# mahirAMPLIFER.net
KiCad netlist of a schematic drawn in Altium Designer
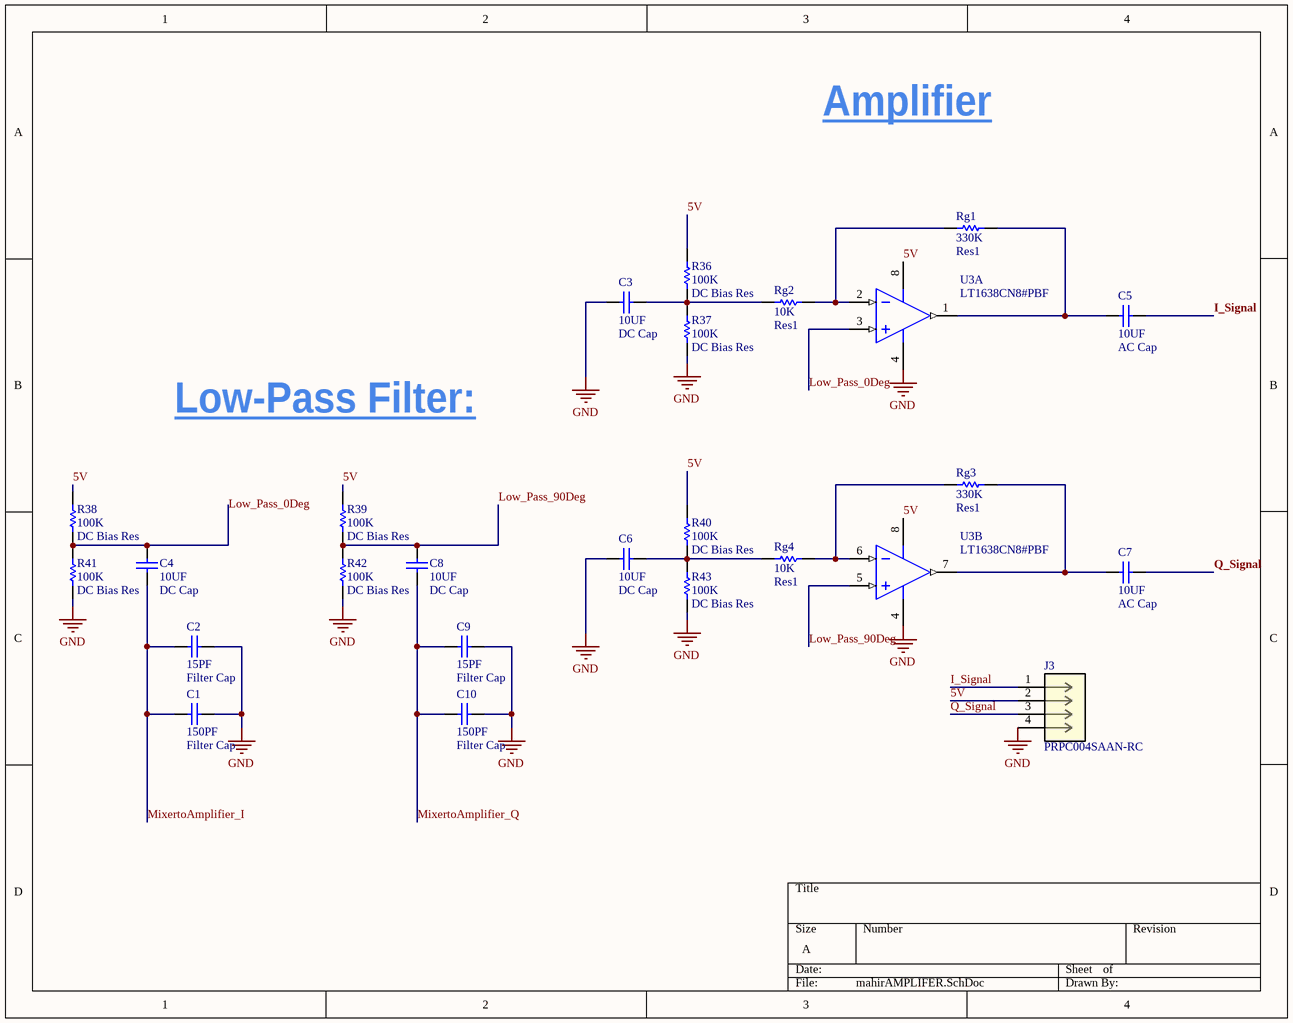
[diagram p0: mahirAMPLIFER.SchDoc]

(export (version "E")
  (design (tool "Eeschema 10.0.6"))
  (components
    (comp (ref "C1")
      (value "Filter Cap")
      (footprint "RADIAL-0.1")
      (description "Capacitor")
      (fields
        (field (name "ALTIUM_VALUE") "150PF")
        (field (name "MANUFACTURER PART NUMBER") "K151J15C0GF53L2")
        (field (name "PUBLISHER") "Altium Limited")
      )
      (libsource (lib "ECE295-Capacitors-TH") (part "CAP CER 150PF 50V C0G/NP0 RADIAL"))
    )
    (comp (ref "C2")
      (value "Filter Cap")
      (footprint "RADIAL-0.1")
      (description "Capacitor")
      (fields
        (field (name "ALTIUM_VALUE") "15PF")
        (field (name "MANUFACTURER PART NUMBER") "K150J15C0GF5TL2")
        (field (name "PUBLISHER") "Altium Limited")
      )
      (libsource (lib "ECE295-Capacitors-TH") (part "CAP CER 15PF 50V C0G/NP0 RADIAL"))
    )
    (comp (ref "C3")
      (value "DC Cap")
      (footprint "RADIAL-0.1")
      (description "Capacitor")
      (fields
        (field (name "ALTIUM_VALUE") "10UF")
        (field (name "MANUFACTURER PART NUMBER") "ESK106M063AC3FA")
        (field (name "PUBLISHER") "Altium Limited")
      )
      (libsource (lib "ECE295-Capacitors-TH") (part "CAP ALUM 10UF 20% 63V RADIAL"))
    )
    (comp (ref "C4")
      (value "DC Cap")
      (footprint "RADIAL-0.1")
      (description "Capacitor")
      (fields
        (field (name "ALTIUM_VALUE") "10UF")
        (field (name "MANUFACTURER PART NUMBER") "ESK106M063AC3FA")
        (field (name "PUBLISHER") "Altium Limited")
      )
      (libsource (lib "ECE295-Capacitors-TH") (part "CAP ALUM 10UF 20% 63V RADIAL"))
    )
    (comp (ref "C5")
      (value "AC Cap")
      (footprint "RADIAL-0.1")
      (description "Capacitor")
      (fields
        (field (name "ALTIUM_VALUE") "10UF")
        (field (name "MANUFACTURER PART NUMBER") "ESK106M063AC3FA")
        (field (name "PUBLISHER") "Altium Limited")
      )
      (libsource (lib "ECE295-Capacitors-TH") (part "CAP ALUM 10UF 20% 63V RADIAL"))
    )
    (comp (ref "C6")
      (value "DC Cap")
      (footprint "RADIAL-0.1")
      (description "Capacitor")
      (fields
        (field (name "ALTIUM_VALUE") "10UF")
        (field (name "MANUFACTURER PART NUMBER") "ESK106M063AC3FA")
        (field (name "PUBLISHER") "Altium Limited")
      )
      (libsource (lib "ECE295-Capacitors-TH") (part "CAP ALUM 10UF 20% 63V RADIAL"))
    )
    (comp (ref "C7")
      (value "AC Cap")
      (footprint "RADIAL-0.1")
      (description "Capacitor")
      (fields
        (field (name "ALTIUM_VALUE") "10UF")
        (field (name "MANUFACTURER PART NUMBER") "ESK106M063AC3FA")
        (field (name "PUBLISHER") "Altium Limited")
      )
      (libsource (lib "ECE295-Capacitors-TH") (part "CAP ALUM 10UF 20% 63V RADIAL"))
    )
    (comp (ref "C8")
      (value "DC Cap")
      (footprint "RADIAL-0.1")
      (description "Capacitor")
      (fields
        (field (name "ALTIUM_VALUE") "10UF")
        (field (name "MANUFACTURER PART NUMBER") "ESK106M063AC3FA")
        (field (name "PUBLISHER") "Altium Limited")
      )
      (libsource (lib "ECE295-Capacitors-TH") (part "CAP ALUM 10UF 20% 63V RADIAL"))
    )
    (comp (ref "C9")
      (value "Filter Cap")
      (footprint "RADIAL-0.1")
      (description "Capacitor")
      (fields
        (field (name "ALTIUM_VALUE") "15PF")
        (field (name "MANUFACTURER PART NUMBER") "K150J15C0GF5TL2")
        (field (name "PUBLISHER") "Altium Limited")
      )
      (libsource (lib "ECE295-Capacitors-TH") (part "CAP CER 15PF 50V C0G/NP0 RADIAL"))
    )
    (comp (ref "C10")
      (value "Filter Cap")
      (footprint "RADIAL-0.1")
      (description "Capacitor")
      (fields
        (field (name "ALTIUM_VALUE") "150PF")
        (field (name "MANUFACTURER PART NUMBER") "K151J15C0GF53L2")
        (field (name "PUBLISHER") "Altium Limited")
      )
      (libsource (lib "ECE295-Capacitors-TH") (part "CAP CER 150PF 50V C0G/NP0 RADIAL"))
    )
    (comp (ref "J3")
      (value "PRPC004SAAN-RC")
      (footprint "CONN4_PRPC004_SUL")
      (description "No Description Available")
      (libsource (lib "PRPC004SAAN-RC") (part "PRPC004SAAN-RC"))
    )
    (comp (ref "R36")
      (value "DC Bias Res")
      (footprint "AXIAL-0.1-RES")
      (description "Resistor")
      (fields
        (field (name "ALTIUM_VALUE") "100K")
        (field (name "MANUFACTURER PART NUMBER") "CFR-25JB-52-100K")
        (field (name "TOLERANCE") "0.05")
        (field (name "PUBLISHER") "Altium Limited")
      )
      (libsource (lib "ECE295-Resistors-TH") (part "RES 100K OHM 5% 1/4W AXIAL"))
    )
    (comp (ref "R37")
      (value "DC Bias Res")
      (footprint "AXIAL-0.1-RES")
      (description "Resistor")
      (fields
        (field (name "ALTIUM_VALUE") "100K")
        (field (name "MANUFACTURER PART NUMBER") "CFR-25JB-52-100K")
        (field (name "TOLERANCE") "0.05")
        (field (name "PUBLISHER") "Altium Limited")
      )
      (libsource (lib "ECE295-Resistors-TH") (part "RES 100K OHM 5% 1/4W AXIAL"))
    )
    (comp (ref "R38")
      (value "DC Bias Res")
      (footprint "AXIAL-0.1-RES")
      (description "Resistor")
      (fields
        (field (name "ALTIUM_VALUE") "100K")
        (field (name "MANUFACTURER PART NUMBER") "CFR-25JB-52-100K")
        (field (name "TOLERANCE") "0.05")
        (field (name "PUBLISHER") "Altium Limited")
      )
      (libsource (lib "ECE295-Resistors-TH") (part "RES 100K OHM 5% 1/4W AXIAL"))
    )
    (comp (ref "R39")
      (value "DC Bias Res")
      (footprint "AXIAL-0.1-RES")
      (description "Resistor")
      (fields
        (field (name "ALTIUM_VALUE") "100K")
        (field (name "MANUFACTURER PART NUMBER") "CFR-25JB-52-100K")
        (field (name "TOLERANCE") "0.05")
        (field (name "PUBLISHER") "Altium Limited")
      )
      (libsource (lib "ECE295-Resistors-TH") (part "RES 100K OHM 5% 1/4W AXIAL"))
    )
    (comp (ref "R40")
      (value "DC Bias Res")
      (footprint "AXIAL-0.1-RES")
      (description "Resistor")
      (fields
        (field (name "ALTIUM_VALUE") "100K")
        (field (name "MANUFACTURER PART NUMBER") "CFR-25JB-52-100K")
        (field (name "TOLERANCE") "0.05")
        (field (name "PUBLISHER") "Altium Limited")
      )
      (libsource (lib "ECE295-Resistors-TH") (part "RES 100K OHM 5% 1/4W AXIAL"))
    )
    (comp (ref "R41")
      (value "DC Bias Res")
      (footprint "AXIAL-0.1-RES")
      (description "Resistor")
      (fields
        (field (name "ALTIUM_VALUE") "100K")
        (field (name "MANUFACTURER PART NUMBER") "CFR-25JB-52-100K")
        (field (name "TOLERANCE") "0.05")
        (field (name "PUBLISHER") "Altium Limited")
      )
      (libsource (lib "ECE295-Resistors-TH") (part "RES 100K OHM 5% 1/4W AXIAL"))
    )
    (comp (ref "R42")
      (value "DC Bias Res")
      (footprint "AXIAL-0.1-RES")
      (description "Resistor")
      (fields
        (field (name "ALTIUM_VALUE") "100K")
        (field (name "MANUFACTURER PART NUMBER") "CFR-25JB-52-100K")
        (field (name "TOLERANCE") "0.05")
        (field (name "PUBLISHER") "Altium Limited")
      )
      (libsource (lib "ECE295-Resistors-TH") (part "RES 100K OHM 5% 1/4W AXIAL"))
    )
    (comp (ref "R43")
      (value "DC Bias Res")
      (footprint "AXIAL-0.1-RES")
      (description "Resistor")
      (fields
        (field (name "ALTIUM_VALUE") "100K")
        (field (name "MANUFACTURER PART NUMBER") "CFR-25JB-52-100K")
        (field (name "TOLERANCE") "0.05")
        (field (name "PUBLISHER") "Altium Limited")
      )
      (libsource (lib "ECE295-Resistors-TH") (part "RES 100K OHM 5% 1/4W AXIAL"))
    )
    (comp (ref "Rg1")
      (value "Res1")
      (footprint "AXIAL-0.1-RES")
      (description "Resistor")
      (fields
        (field (name "ALTIUM_VALUE") "330K")
        (field (name "MANUFACTURER PART NUMBER") "CFR-25JB-52-330K")
        (field (name "TOLERANCE") "0.05")
        (field (name "PUBLISHER") "Altium Limited")
      )
      (libsource (lib "ECE295-Resistors-TH") (part "RES 330K OHM 5% 1/4W AXIAL"))
    )
    (comp (ref "Rg2")
      (value "Res1")
      (footprint "AXIAL-0.1-RES")
      (description "Resistor")
      (fields
        (field (name "ALTIUM_VALUE") "10K")
        (field (name "MANUFACTURER PART NUMBER") "CFR-25JB-52-10K")
        (field (name "TOLERANCE") "0.05")
        (field (name "PUBLISHER") "Altium Limited")
      )
      (libsource (lib "ECE295-Resistors-TH") (part "RES 10K OHM 5% 1/4W AXIAL"))
    )
    (comp (ref "Rg3")
      (value "Res1")
      (footprint "AXIAL-0.1-RES")
      (description "Resistor")
      (fields
        (field (name "ALTIUM_VALUE") "330K")
        (field (name "MANUFACTURER PART NUMBER") "CFR-25JB-52-330K")
        (field (name "TOLERANCE") "0.05")
        (field (name "PUBLISHER") "Altium Limited")
      )
      (libsource (lib "ECE295-Resistors-TH") (part "RES 330K OHM 5% 1/4W AXIAL"))
    )
    (comp (ref "Rg4")
      (value "Res1")
      (footprint "AXIAL-0.1-RES")
      (description "Resistor")
      (fields
        (field (name "ALTIUM_VALUE") "10K")
        (field (name "MANUFACTURER PART NUMBER") "CFR-25JB-52-10K")
        (field (name "TOLERANCE") "0.05")
        (field (name "PUBLISHER") "Altium Limited")
      )
      (libsource (lib "ECE295-Resistors-TH") (part "RES 10K OHM 5% 1/4W AXIAL"))
    )
    (comp (ref "U3")
      (value "LT1638CN8#PBF")
      (footprint "LT-N8-8")
      (fields
        (field (name "MANUFACTURER") "Linear Technology")
        (field (name "LINEAR TECHNOLOGY PART NUMBER") "LT1638")
      )
      (libsource (lib "Altium Content Vault") (part "LT-LT1638-N8-8"))
    )
  )
  (nets
    (net (code "1") (name "/5V") (class "Default")
      (node (ref "J3") (pin "2") (pinfunction "2_2") (pintype "passive"))
      (node (ref "R36") (pin "2") (pinfunction "2_2") (pintype "passive"))
      (node (ref "R38") (pin "2") (pinfunction "2_2") (pintype "passive"))
      (node (ref "R39") (pin "2") (pinfunction "2_2") (pintype "passive"))
      (node (ref "R40") (pin "2") (pinfunction "2_2") (pintype "passive"))
      (node (ref "U3") (pin "8") (pinfunction "V+_8") (pintype "power_in"))
    )
    (net (code "2") (name "/I_Signal") (class "Default")
      (node (ref "C5") (pin "1") (pinfunction "1_1") (pintype "passive"))
      (node (ref "J3") (pin "1") (pinfunction "1_1") (pintype "passive"))
    )
    (net (code "3") (name "/Low_Pass_0Deg") (class "Default")
      (node (ref "C4") (pin "2") (pinfunction "2_2") (pintype "passive"))
      (node (ref "R38") (pin "1") (pinfunction "1_1") (pintype "passive"))
      (node (ref "R41") (pin "2") (pinfunction "2_2") (pintype "passive"))
      (node (ref "U3") (pin "3") (pinfunction "+IN_A_3") (pintype "input"))
    )
    (net (code "4") (name "/Low_Pass_90Deg") (class "Default")
      (node (ref "C8") (pin "2") (pinfunction "2_2") (pintype "passive"))
      (node (ref "R39") (pin "1") (pinfunction "1_1") (pintype "passive"))
      (node (ref "R42") (pin "2") (pinfunction "2_2") (pintype "passive"))
      (node (ref "U3") (pin "5") (pinfunction "+IN_B_5") (pintype "input"))
    )
    (net (code "5") (name "/MixertoAmplifier_I") (class "Default")
      (node (ref "C1") (pin "1") (pinfunction "1_1") (pintype "passive"))
      (node (ref "C2") (pin "1") (pinfunction "1_1") (pintype "passive"))
      (node (ref "C4") (pin "1") (pinfunction "1_1") (pintype "passive"))
    )
    (net (code "6") (name "/MixertoAmplifier_Q") (class "Default")
      (node (ref "C10") (pin "1") (pinfunction "1_1") (pintype "passive"))
      (node (ref "C8") (pin "1") (pinfunction "1_1") (pintype "passive"))
      (node (ref "C9") (pin "1") (pinfunction "1_1") (pintype "passive"))
    )
    (net (code "7") (name "/Q_Signal") (class "Default")
      (node (ref "C7") (pin "1") (pinfunction "1_1") (pintype "passive"))
      (node (ref "J3") (pin "3") (pinfunction "3_3") (pintype "passive"))
    )
    (net (code "8") (name "GND") (class "Default")
      (node (ref "C1") (pin "2") (pinfunction "2_2") (pintype "passive"))
      (node (ref "C10") (pin "2") (pinfunction "2_2") (pintype "passive"))
      (node (ref "C2") (pin "2") (pinfunction "2_2") (pintype "passive"))
      (node (ref "C3") (pin "2") (pinfunction "2_2") (pintype "passive"))
      (node (ref "C6") (pin "2") (pinfunction "2_2") (pintype "passive"))
      (node (ref "C9") (pin "2") (pinfunction "2_2") (pintype "passive"))
      (node (ref "J3") (pin "4") (pinfunction "4_4") (pintype "passive"))
      (node (ref "R37") (pin "1") (pinfunction "1_1") (pintype "passive"))
      (node (ref "R41") (pin "1") (pinfunction "1_1") (pintype "passive"))
      (node (ref "R42") (pin "1") (pinfunction "1_1") (pintype "passive"))
      (node (ref "R43") (pin "1") (pinfunction "1_1") (pintype "passive"))
      (node (ref "U3") (pin "4") (pinfunction "V-_4") (pintype "power_in"))
    )
    (net (code "9") (name "Net-(C3-Pad1)") (class "Default")
      (node (ref "C3") (pin "1") (pinfunction "1_1") (pintype "passive"))
      (node (ref "R36") (pin "1") (pinfunction "1_1") (pintype "passive"))
      (node (ref "R37") (pin "2") (pinfunction "2_2") (pintype "passive"))
      (node (ref "Rg2") (pin "1") (pinfunction "1_1") (pintype "passive"))
    )
    (net (code "10") (name "Net-(C6-Pad1)") (class "Default")
      (node (ref "C6") (pin "1") (pinfunction "1_1") (pintype "passive"))
      (node (ref "R40") (pin "1") (pinfunction "1_1") (pintype "passive"))
      (node (ref "R43") (pin "2") (pinfunction "2_2") (pintype "passive"))
      (node (ref "Rg4") (pin "1") (pinfunction "1_1") (pintype "passive"))
    )
    (net (code "11") (name "Net-(U3A--IN_A)") (class "Default")
      (node (ref "Rg1") (pin "1") (pinfunction "1_1") (pintype "passive"))
      (node (ref "Rg2") (pin "2") (pinfunction "2_2") (pintype "passive"))
      (node (ref "U3") (pin "2") (pinfunction "-IN_A_2") (pintype "input"))
    )
    (net (code "12") (name "Net-(U3A-OUT_A)") (class "Default")
      (node (ref "C5") (pin "2") (pinfunction "2_2") (pintype "passive"))
      (node (ref "Rg1") (pin "2") (pinfunction "2_2") (pintype "passive"))
      (node (ref "U3") (pin "1") (pinfunction "OUT_A_1") (pintype "output"))
    )
    (net (code "13") (name "Net-(U3B--IN_B)") (class "Default")
      (node (ref "Rg3") (pin "1") (pinfunction "1_1") (pintype "passive"))
      (node (ref "Rg4") (pin "2") (pinfunction "2_2") (pintype "passive"))
      (node (ref "U3") (pin "6") (pinfunction "-IN_B_6") (pintype "input"))
    )
    (net (code "14") (name "Net-(U3B-OUT_B)") (class "Default")
      (node (ref "C7") (pin "2") (pinfunction "2_2") (pintype "passive"))
      (node (ref "Rg3") (pin "2") (pinfunction "2_2") (pintype "passive"))
      (node (ref "U3") (pin "7") (pinfunction "OUT_B_7") (pintype "output"))
    )
  )
)
